# ll_both.net
KiCad netlist of a schematic drawn in EAGLE
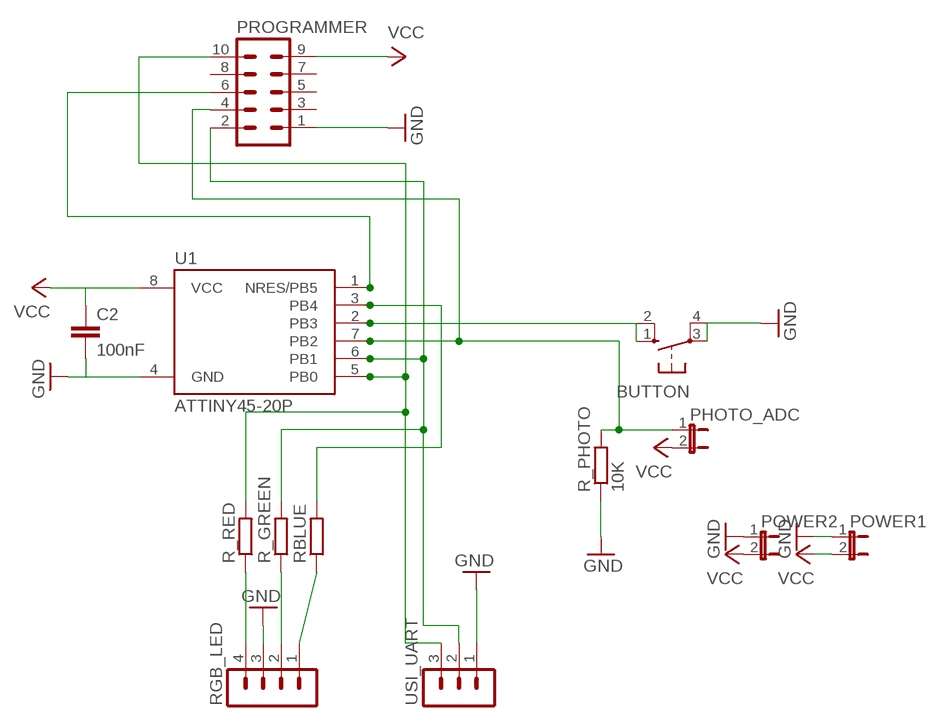
[diagram p0: schematic, sheet 1]

(export (version "E")
  (design (tool "Eeschema 10.0.6"))
  (components
    (comp (ref "BUTTON")
      (value "10-XX")
      (footprint "eagle-import:B3F-10XX")
      (fields (field (name "MPN") "B3F-1000"))
      (libsource (lib "eagle-import") (part "10-XX"))
    )
    (comp (ref "C2")
      (value "100nF")
      (footprint "eagle-import:C025-025X050")
      (libsource (lib "eagle-import") (part "C-EU025-025X050"))
    )
    (comp (ref "PHOTO_ADC")
      (value "JP1E")
      (footprint "eagle-import:JP1")
      (libsource (lib "eagle-import") (part "JP1E"))
    )
    (comp (ref "POWER1")
      (value "JP1E")
      (footprint "eagle-import:JP1")
      (libsource (lib "eagle-import") (part "JP1E"))
    )
    (comp (ref "POWER2")
      (value "JP1E")
      (footprint "eagle-import:JP1")
      (libsource (lib "eagle-import") (part "JP1E"))
    )
    (comp (ref "PROGRAMMER")
      (value "MA05-2")
      (footprint "eagle-import:MA05-2")
      (libsource (lib "eagle-import") (part "MA05-2"))
    )
    (comp (ref "RBLUE")
      (value "R-EU_0204/7")
      (footprint "eagle-import:0204_7")
      (libsource (lib "eagle-import") (part "R-EU_0204/7"))
    )
    (comp (ref "RGB_LED")
      (value "MA04-1")
      (footprint "eagle-import:MA04-1")
      (libsource (lib "eagle-import") (part "MA04-1"))
    )
    (comp (ref "R_GREEN")
      (value "R-EU_0204/7")
      (footprint "eagle-import:0204_7")
      (libsource (lib "eagle-import") (part "R-EU_0204/7"))
    )
    (comp (ref "R_PHOTO")
      (value "10K")
      (footprint "eagle-import:0204_7")
      (libsource (lib "eagle-import") (part "R-EU_0204/7"))
    )
    (comp (ref "R_RED")
      (value "R-EU_0204/7")
      (footprint "eagle-import:0204_7")
      (libsource (lib "eagle-import") (part "R-EU_0204/7"))
    )
    (comp (ref "U1")
      (value "ATTINY45-20P")
      (footprint "eagle-import:PDIP08_300MIL")
      (libsource (lib "eagle-import") (part "ATTINY45P-20"))
    )
    (comp (ref "USI_UART")
      (value "MA03-1")
      (footprint "eagle-import:MA03-1")
      (libsource (lib "eagle-import") (part "MA03-1"))
    )
  )
  (nets
    (net (code "1") (name "GND") (class "Default")
      (node (ref "BUTTON") (pin "3") (pinfunction "P_3") (pintype "passive"))
      (node (ref "BUTTON") (pin "4") (pinfunction "P1_4") (pintype "passive"))
      (node (ref "C2") (pin "2") (pinfunction "2_2") (pintype "passive"))
      (node (ref "POWER1") (pin "1") (pinfunction "1_1") (pintype "passive"))
      (node (ref "POWER2") (pin "1") (pinfunction "1_1") (pintype "passive"))
      (node (ref "PROGRAMMER") (pin "1") (pinfunction "1_1") (pintype "passive"))
      (node (ref "RGB_LED") (pin "3") (pinfunction "3_3") (pintype "passive"))
      (node (ref "R_PHOTO") (pin "1") (pinfunction "1_1") (pintype "passive"))
      (node (ref "U1") (pin "4") (pinfunction "GND_4") (pintype "power_in"))
      (node (ref "USI_UART") (pin "1") (pinfunction "1_1") (pintype "passive"))
    )
    (net (code "2") (name "Net-(BUTTON-S)") (class "Default")
      (node (ref "BUTTON") (pin "1") (pinfunction "S_1") (pintype "passive"))
      (node (ref "BUTTON") (pin "2") (pinfunction "S1_2") (pintype "passive"))
      (node (ref "U1") (pin "2") (pinfunction "PB3_2") (pintype "bidirectional"))
    )
    (net (code "3") (name "Net-(RBLUE-Pad1)") (class "Default")
      (node (ref "RBLUE") (pin "1") (pinfunction "1_1") (pintype "passive"))
      (node (ref "RGB_LED") (pin "1") (pinfunction "1_1") (pintype "passive"))
    )
    (net (code "4") (name "Net-(RGB_LED-Pad2)") (class "Default")
      (node (ref "RGB_LED") (pin "2") (pinfunction "2_2") (pintype "passive"))
      (node (ref "R_GREEN") (pin "1") (pinfunction "1_1") (pintype "passive"))
    )
    (net (code "5") (name "Net-(RGB_LED-Pad4)") (class "Default")
      (node (ref "RGB_LED") (pin "4") (pinfunction "4_4") (pintype "passive"))
      (node (ref "R_RED") (pin "1") (pinfunction "1_1") (pintype "passive"))
    )
    (net (code "6") (name "Net-(U1-NRES{slash}PB5)") (class "Default")
      (node (ref "PROGRAMMER") (pin "6") (pinfunction "6_6") (pintype "passive"))
      (node (ref "U1") (pin "1") (pinfunction "NRES/PB5_1") (pintype "bidirectional"))
    )
    (net (code "7") (name "Net-(U1-PB0)") (class "Default")
      (node (ref "PROGRAMMER") (pin "10") (pinfunction "10_10") (pintype "passive"))
      (node (ref "R_RED") (pin "2") (pinfunction "2_2") (pintype "passive"))
      (node (ref "U1") (pin "5") (pinfunction "PB0_5") (pintype "bidirectional"))
      (node (ref "USI_UART") (pin "3") (pinfunction "3_3") (pintype "passive"))
    )
    (net (code "8") (name "Net-(U1-PB1)") (class "Default")
      (node (ref "PROGRAMMER") (pin "2") (pinfunction "2_2") (pintype "passive"))
      (node (ref "R_GREEN") (pin "2") (pinfunction "2_2") (pintype "passive"))
      (node (ref "U1") (pin "6") (pinfunction "PB1_6") (pintype "bidirectional"))
      (node (ref "USI_UART") (pin "2") (pinfunction "2_2") (pintype "passive"))
    )
    (net (code "9") (name "Net-(U1-PB2)") (class "Default")
      (node (ref "PHOTO_ADC") (pin "1") (pinfunction "1_1") (pintype "passive"))
      (node (ref "PROGRAMMER") (pin "4") (pinfunction "4_4") (pintype "passive"))
      (node (ref "R_PHOTO") (pin "2") (pinfunction "2_2") (pintype "passive"))
      (node (ref "U1") (pin "7") (pinfunction "PB2_7") (pintype "bidirectional"))
    )
    (net (code "10") (name "Net-(U1-PB4)") (class "Default")
      (node (ref "RBLUE") (pin "2") (pinfunction "2_2") (pintype "passive"))
      (node (ref "U1") (pin "3") (pinfunction "PB4_3") (pintype "bidirectional"))
    )
    (net (code "11") (name "VCC") (class "Default")
      (node (ref "C2") (pin "1") (pinfunction "1_1") (pintype "passive"))
      (node (ref "PHOTO_ADC") (pin "2") (pinfunction "2_2") (pintype "passive"))
      (node (ref "POWER1") (pin "2") (pinfunction "2_2") (pintype "passive"))
      (node (ref "POWER2") (pin "2") (pinfunction "2_2") (pintype "passive"))
      (node (ref "PROGRAMMER") (pin "9") (pinfunction "9_9") (pintype "passive"))
      (node (ref "U1") (pin "8") (pinfunction "VCC_8") (pintype "power_in"))
    )
    (net (code "12") (name "unconnected-(PROGRAMMER-Pad3)") (class "Default")
      (node (ref "PROGRAMMER") (pin "3") (pinfunction "3_3") (pintype "passive"))
    )
    (net (code "13") (name "unconnected-(PROGRAMMER-Pad5)") (class "Default")
      (node (ref "PROGRAMMER") (pin "5") (pinfunction "5_5") (pintype "passive"))
    )
    (net (code "14") (name "unconnected-(PROGRAMMER-Pad7)") (class "Default")
      (node (ref "PROGRAMMER") (pin "7") (pinfunction "7_7") (pintype "passive"))
    )
    (net (code "15") (name "unconnected-(PROGRAMMER-Pad8)") (class "Default")
      (node (ref "PROGRAMMER") (pin "8") (pinfunction "8_8") (pintype "passive"))
    )
  )
)
